# Power.net
KiCad netlist of a schematic drawn in Altium Designer
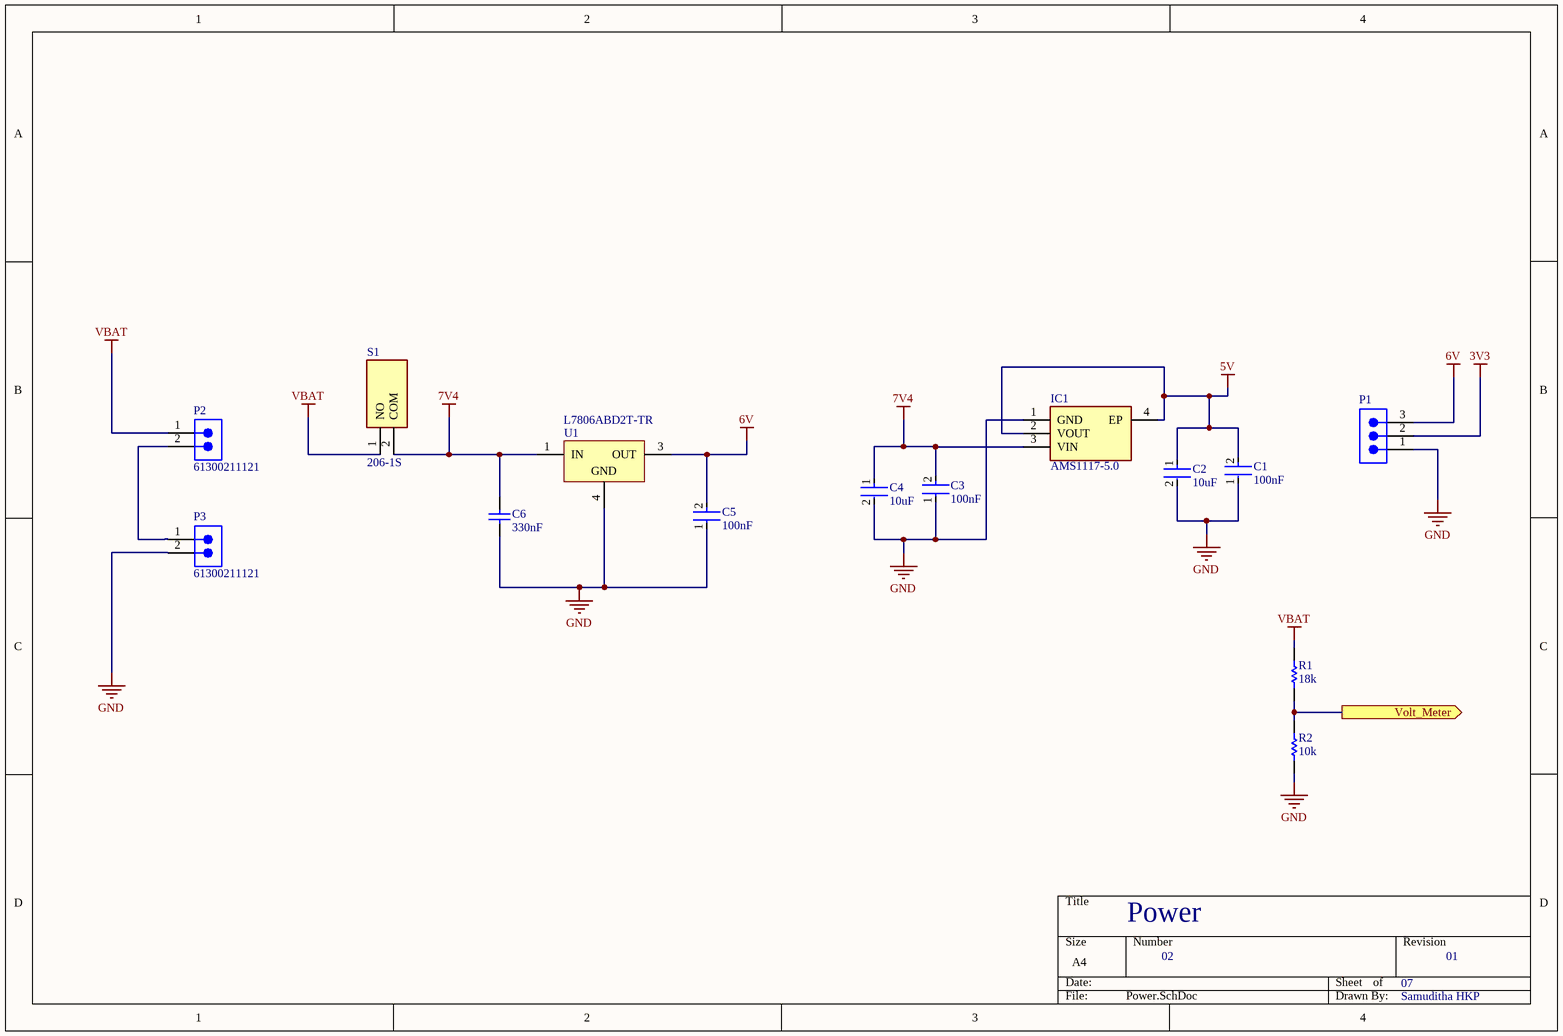
[diagram p0: Power.SchDoc]

(export (version "E")
  (design (tool "Eeschema 10.0.6"))
  (components
    (comp (ref "C1")
      (value "100nF")
      (footprint "FP-GRM15-MFG")
      (description "CAP CER 0.1UF 16V X7R 0402")
      (fields (field (name "MANUFACTURER PART NUMBER") "GRM155R71C104KA88D") (field (name "TOLERANCE") "10%"))
      (libsource (lib "Altium Content Vault") (part "236180d848d6139a670b325ea6854c9"))
    )
    (comp (ref "C2")
      (value "10uF")
      (footprint "FP-GRM155-0_15-IPC_B")
      (description "Chip Multilayer Ceramic Capacitors for General Purpose, 0402, 10uF, X5R, 15%, 20%, 6.3V")
      (fields (field (name "TOLERANCE") "20%"))
      (libsource (lib "Altium Content Vault") (part "b4654b650e69147ec39a6b967a45e02"))
    )
    (comp (ref "C3")
      (value "100nF")
      (footprint "FP-GRM15-MFG")
      (description "CAP CER 0.1UF 16V X7R 0402")
      (fields (field (name "MANUFACTURER PART NUMBER") "GRM155R71C104KA88D") (field (name "TOLERANCE") "10%"))
      (libsource (lib "Altium Content Vault") (part "236180d848d6139a670b325ea6854c9"))
    )
    (comp (ref "C4")
      (value "10uF")
      (footprint "FP-GRM155-0_15-IPC_B")
      (description "Chip Multilayer Ceramic Capacitors for General Purpose, 0402, 10uF, X5R, 15%, 20%, 6.3V")
      (fields (field (name "TOLERANCE") "20%"))
      (libsource (lib "Altium Content Vault") (part "b4654b650e69147ec39a6b967a45e02"))
    )
    (comp (ref "C5")
      (value "100nF")
      (footprint "FP-GRM15-MFG")
      (description "CAP CER 0.1UF 16V X7R 0402")
      (fields (field (name "MANUFACTURER PART NUMBER") "GRM155R71C104KA88D") (field (name "TOLERANCE") "10%"))
      (libsource (lib "Altium Content Vault") (part "236180d848d6139a670b325ea6854c9"))
    )
    (comp (ref "C6")
      (value "330nF")
      (footprint "CAPC1005X55X25ML05T10")
      (fields (field (name "PART NUMBER") "GRM155R61A334KE15D") (field (name "MANUFACTURER") "Murata"))
      (libsource (lib "Altium Content Vault") (part "CAP"))
    )
    (comp (ref "IC1")
      (value "AMS1117-5.0")
      (footprint "SamacSys:SOT290P700X180-4N")
      (description "Integrated Circuit")
      (libsource (lib "*") (part "AMS1117-5.0"))
    )
    (comp (ref "P1")
      (value "61300311021")
      (footprint "61300311021")
      (libsource (lib "Altium Content Vault") (part "Header_Male_1R_03P"))
    )
    (comp (ref "P2")
      (value "61300211121")
      (footprint "61300211121")
      (libsource (lib "Altium Content Vault") (part "Header_Male_1R_02P"))
    )
    (comp (ref "P3")
      (value "61300211121")
      (footprint "61300211121")
      (libsource (lib "Altium Content Vault") (part "Header_Male_1R_02P"))
    )
    (comp (ref "R1")
      (value "18k")
      (footprint "RESC1005X40X25LL05T10")
      (fields (field (name "PART NUMBER") "RC0402FR-0718KL") (field (name "MANUFACTURER") "Yageo / Phycomp"))
      (libsource (lib "Altium Content Vault") (part "RES"))
    )
    (comp (ref "R2")
      (value "10k")
      (footprint "RESC1005X40X25LL05T10")
      (fields (field (name "PART NUMBER") "RC0402FR-0710KL") (field (name "MANUFACTURER") "Yageo / Phycomp"))
      (libsource (lib "Altium Content Vault") (part "RES"))
    )
    (comp (ref "S1")
      (value "206-1S")
      (footprint "SamacSys:2061S")
      (description "Switch")
      (libsource (lib "*") (part "206-1S"))
    )
    (comp (ref "U1")
      (value "L7806ABD2T-TR")
      (footprint "TO-263_N")
      (description "Positive Voltage Regulator, 3-Pin D2PAK, Tape and Reel")
      (libsource (lib "Altium Content Vault") (part "PM-REG-L4940-SOT3"))
    )
  )
  (nets
    (net (code "1") (name "/Volt_Meter") (class "Default")
      (node (ref "R1") (pin "1") (pinfunction "1_1") (pintype "passive"))
      (node (ref "R2") (pin "2") (pinfunction "2_2") (pintype "passive"))
    )
    (net (code "2") (name "3V3") (class "Default")
      (node (ref "P1") (pin "2") (pinfunction "2_2") (pintype "passive"))
    )
    (net (code "3") (name "5V") (class "Default")
      (node (ref "C1") (pin "2") (pinfunction "2_2") (pintype "passive"))
      (node (ref "C2") (pin "1") (pinfunction "1_1") (pintype "passive"))
      (node (ref "IC1") (pin "2") (pinfunction "VOUT_2") (pintype "passive"))
      (node (ref "IC1") (pin "4") (pinfunction "EP_4") (pintype "passive"))
    )
    (net (code "4") (name "6V") (class "Default")
      (node (ref "C5") (pin "2") (pinfunction "2_2") (pintype "passive"))
      (node (ref "P1") (pin "3") (pinfunction "3_3") (pintype "passive"))
      (node (ref "U1") (pin "3") (pinfunction "OUT_3") (pintype "power_in"))
    )
    (net (code "5") (name "7V4") (class "Default")
      (node (ref "C3") (pin "2") (pinfunction "2_2") (pintype "passive"))
      (node (ref "C4") (pin "1") (pinfunction "1_1") (pintype "passive"))
      (node (ref "C6") (pin "2") (pinfunction "2_2") (pintype "passive"))
      (node (ref "IC1") (pin "3") (pinfunction "VIN_3") (pintype "passive"))
      (node (ref "S1") (pin "2") (pinfunction "COM_2") (pintype "passive"))
      (node (ref "U1") (pin "1") (pinfunction "IN_1") (pintype "power_in"))
    )
    (net (code "6") (name "GND") (class "Default")
      (node (ref "C1") (pin "1") (pinfunction "1_1") (pintype "passive"))
      (node (ref "C2") (pin "2") (pinfunction "2_2") (pintype "passive"))
      (node (ref "C3") (pin "1") (pinfunction "1_1") (pintype "passive"))
      (node (ref "C4") (pin "2") (pinfunction "2_2") (pintype "passive"))
      (node (ref "C5") (pin "1") (pinfunction "1_1") (pintype "passive"))
      (node (ref "C6") (pin "1") (pinfunction "1_1") (pintype "passive"))
      (node (ref "IC1") (pin "1") (pinfunction "GND_1") (pintype "passive"))
      (node (ref "P1") (pin "1") (pinfunction "1_1") (pintype "passive"))
      (node (ref "P3") (pin "2") (pinfunction "2_2") (pintype "passive"))
      (node (ref "R2") (pin "1") (pinfunction "1_1") (pintype "passive"))
      (node (ref "U1") (pin "4") (pinfunction "GND_4") (pintype "power_in"))
    )
    (net (code "7") (name "Net-(P2-Pad2)") (class "Default")
      (node (ref "P2") (pin "2") (pinfunction "2_2") (pintype "passive"))
      (node (ref "P3") (pin "1") (pinfunction "1_1") (pintype "passive"))
    )
    (net (code "8") (name "VBAT") (class "Default")
      (node (ref "P2") (pin "1") (pinfunction "1_1") (pintype "passive"))
      (node (ref "R1") (pin "2") (pinfunction "2_2") (pintype "passive"))
      (node (ref "S1") (pin "1") (pinfunction "NO_1") (pintype "passive"))
    )
  )
)
